# eth2rs485.net
KiCad netlist of a schematic drawn in EAGLE
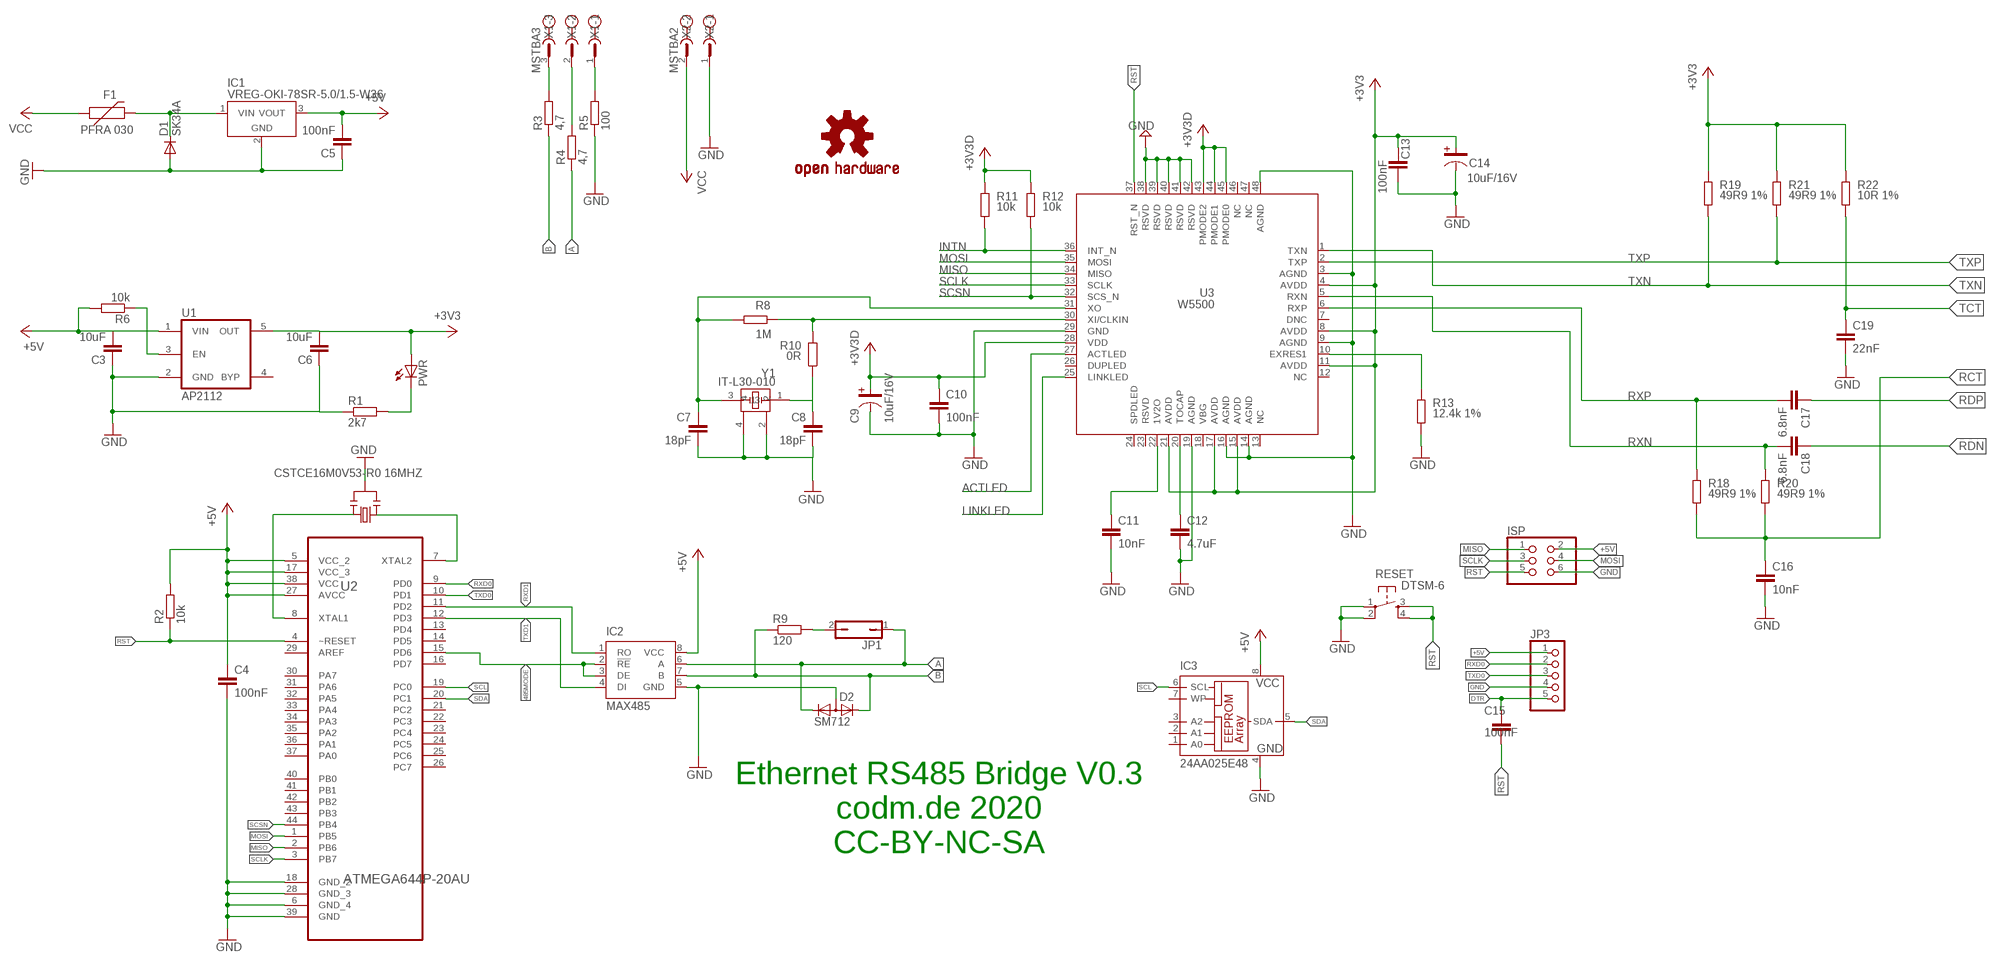
[diagram p0: schematic, sheet 1, part 1 of 2]
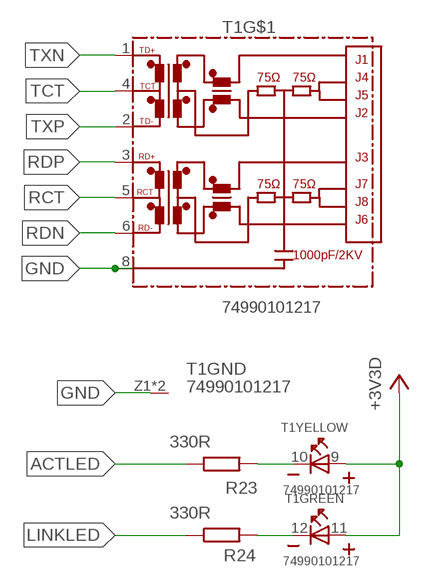
[diagram p1: schematic, sheet 1, part 2 of 2]

(export (version "E")
  (design (tool "Eeschema 10.0.6"))
  (components
    (comp (ref "C3")
      (value "10uF")
      (footprint "eagle-import:C0805")
      (libsource (lib "eagle-import") (part "C-EUC0805"))
    )
    (comp (ref "C4")
      (value "100nF")
      (footprint "eagle-import:C0805")
      (libsource (lib "eagle-import") (part "C-EUC0805"))
    )
    (comp (ref "C5")
      (value "100nF")
      (footprint "eagle-import:C0805")
      (libsource (lib "eagle-import") (part "C-EUC0805"))
    )
    (comp (ref "C6")
      (value "10uF")
      (footprint "eagle-import:C0805")
      (libsource (lib "eagle-import") (part "C-EUC0805"))
    )
    (comp (ref "C7")
      (value "18pF")
      (footprint "eagle-import:C0805")
      (libsource (lib "eagle-import") (part "C-EUC0805"))
    )
    (comp (ref "C8")
      (value "18pF")
      (footprint "eagle-import:C0805")
      (libsource (lib "eagle-import") (part "C-EUC0805"))
    )
    (comp (ref "C9")
      (value "10uF/16V")
      (footprint "eagle-import:C-3216(TANTAL)")
      (libsource (lib "eagle-import") (part "C-3216(TANTAL)"))
    )
    (comp (ref "C10")
      (value "100nF")
      (footprint "eagle-import:C0805")
      (libsource (lib "eagle-import") (part "C-EUC0805"))
    )
    (comp (ref "C11")
      (value "10nF")
      (footprint "eagle-import:C0805")
      (libsource (lib "eagle-import") (part "C-EUC0805"))
    )
    (comp (ref "C12")
      (value "4.7uF")
      (footprint "eagle-import:C0805")
      (libsource (lib "eagle-import") (part "C-EUC0805"))
    )
    (comp (ref "C13")
      (value "100nF")
      (footprint "eagle-import:C0805")
      (libsource (lib "eagle-import") (part "C-EUC0805"))
    )
    (comp (ref "C14")
      (value "10uF/16V")
      (footprint "eagle-import:C-3216(TANTAL)")
      (libsource (lib "eagle-import") (part "C-3216(TANTAL)"))
    )
    (comp (ref "C15")
      (value "100nF")
      (footprint "eagle-import:C0805")
      (libsource (lib "eagle-import") (part "C-EUC0805"))
    )
    (comp (ref "C16")
      (value "10nF")
      (footprint "eagle-import:C0805")
      (libsource (lib "eagle-import") (part "C-EUC0805"))
    )
    (comp (ref "C17")
      (value "6.8nF")
      (footprint "eagle-import:C0805")
      (libsource (lib "eagle-import") (part "C-EUC0805"))
    )
    (comp (ref "C18")
      (value "6.8nF")
      (footprint "eagle-import:C0805")
      (libsource (lib "eagle-import") (part "C-EUC0805"))
    )
    (comp (ref "C19")
      (value "22nF")
      (footprint "eagle-import:C0805")
      (libsource (lib "eagle-import") (part "C-EUC0805"))
    )
    (comp (ref "D1")
      (value "SK34A")
      (footprint "eagle-import:DO214AC")
      (libsource (lib "eagle-import") (part "DIODE-DO214AC"))
    )
    (comp (ref "D2")
      (value "SM712")
      (footprint "eagle-import:SOT23")
      (libsource (lib "eagle-import") (part "DIODE-2CA|ACSOT23"))
    )
    (comp (ref "F1")
      (value "PFRA 030")
      (footprint "eagle-import:PTH")
      (libsource (lib "eagle-import") (part "PPTC_PTH"))
    )
    (comp (ref "IC1")
      (value "VREG-OKI-78SR-5.0/1.5-W36")
      (footprint "eagle-import:OKI-78SR")
      (libsource (lib "eagle-import") (part "VREG-OKI-78SR-5.0/1.5-W36"))
    )
    (comp (ref "IC2")
      (value "MAX485")
      (footprint "eagle-import:SOIC8")
      (libsource (lib "eagle-import") (part "LTC485S"))
    )
    (comp (ref "IC3")
      (value "24AA025E48")
      (footprint "eagle-import:SO-08")
      (fields (field (name "MPN") "24AA02/SN"))
      (libsource (lib "eagle-import") (part "24SNAA02"))
    )
    (comp (ref "ISP")
      (value "PINHD-2X3")
      (footprint "eagle-import:2X03")
      (libsource (lib "eagle-import") (part "PINHD-2X3"))
    )
    (comp (ref "JP1")
      (value "JP1Q")
      (footprint "eagle-import:JP1")
      (libsource (lib "eagle-import") (part "JP1Q"))
    )
    (comp (ref "JP3")
      (value "PINHD-1X5")
      (footprint "eagle-import:1X05")
      (libsource (lib "eagle-import") (part "PINHD-1X5"))
    )
    (comp (ref "LOGO1")
      (value "OSHW-LOGOM")
      (footprint "eagle-import:OSHW-LOGO-M")
      (libsource (lib "eagle-import") (part "OSHW-LOGOM"))
    )
    (comp (ref "PWR")
      (value "LEDCHIP-LED0805")
      (footprint "eagle-import:CHIP-LED0805")
      (libsource (lib "eagle-import") (part "LEDCHIP-LED0805"))
    )
    (comp (ref "R1")
      (value "2k7")
      (footprint "eagle-import:R0805")
      (libsource (lib "eagle-import") (part "R-EU_R0805"))
    )
    (comp (ref "R2")
      (value "10k")
      (footprint "eagle-import:R0805")
      (libsource (lib "eagle-import") (part "R-EU_R0805"))
    )
    (comp (ref "R3")
      (value "4,7")
      (footprint "eagle-import:R0805")
      (libsource (lib "eagle-import") (part "R-EU_R0805"))
    )
    (comp (ref "R4")
      (value "4,7")
      (footprint "eagle-import:R0805")
      (libsource (lib "eagle-import") (part "R-EU_R0805"))
    )
    (comp (ref "R5")
      (value "100")
      (footprint "eagle-import:R0805")
      (libsource (lib "eagle-import") (part "R-EU_R0805"))
    )
    (comp (ref "R6")
      (value "10k")
      (footprint "eagle-import:R0805")
      (libsource (lib "eagle-import") (part "R-EU_R0805"))
    )
    (comp (ref "R8")
      (value "1M")
      (footprint "eagle-import:R0805")
      (libsource (lib "eagle-import") (part "R-EU_R0805"))
    )
    (comp (ref "R9")
      (value "120")
      (footprint "eagle-import:R0805")
      (libsource (lib "eagle-import") (part "R-EU_R0805"))
    )
    (comp (ref "R10")
      (value "0R")
      (footprint "eagle-import:R0805")
      (libsource (lib "eagle-import") (part "R-EU_R0805"))
    )
    (comp (ref "R11")
      (value "10k")
      (footprint "eagle-import:R0805")
      (libsource (lib "eagle-import") (part "R-EU_R0805"))
    )
    (comp (ref "R12")
      (value "10k")
      (footprint "eagle-import:R0805")
      (libsource (lib "eagle-import") (part "R-EU_R0805"))
    )
    (comp (ref "R13")
      (value "12.4k 1%")
      (footprint "eagle-import:R0805")
      (libsource (lib "eagle-import") (part "R-EU_R0805"))
    )
    (comp (ref "R18")
      (value "49R9 1%")
      (footprint "eagle-import:R0805")
      (libsource (lib "eagle-import") (part "R-EU_R0805"))
    )
    (comp (ref "R19")
      (value "49R9 1%")
      (footprint "eagle-import:R0805")
      (libsource (lib "eagle-import") (part "R-EU_R0805"))
    )
    (comp (ref "R20")
      (value "49R9 1%")
      (footprint "eagle-import:R0805")
      (libsource (lib "eagle-import") (part "R-EU_R0805"))
    )
    (comp (ref "R21")
      (value "49R9 1%")
      (footprint "eagle-import:R0805")
      (libsource (lib "eagle-import") (part "R-EU_R0805"))
    )
    (comp (ref "R22")
      (value "10R 1%")
      (footprint "eagle-import:R0805")
      (libsource (lib "eagle-import") (part "R-EU_R0805"))
    )
    (comp (ref "R23")
      (value "330R")
      (footprint "eagle-import:R0805")
      (libsource (lib "eagle-import") (part "R-EU_R0805"))
    )
    (comp (ref "R24")
      (value "330R")
      (footprint "eagle-import:R0805")
      (libsource (lib "eagle-import") (part "R-EU_R0805"))
    )
    (comp (ref "RESET")
      (value "DTSM-6")
      (footprint "eagle-import:DTSM-6")
      (libsource (lib "eagle-import") (part "DTSM-6"))
    )
    (comp (ref "T1")
      (value "74990101217")
      (footprint "eagle-import:74990111217")
      (libsource (lib "eagle-import") (part "WE-RJ45_74990111217"))
    )
    (comp (ref "U1")
      (value "AP2112")
      (footprint "eagle-import:SOT23-5")
      (libsource (lib "eagle-import") (part "AP2210K"))
    )
    (comp (ref "U2")
      (value "ATMEGA644P-20AU")
      (footprint "eagle-import:QFP80P1200X1200X120-44N")
      (libsource (lib "eagle-import") (part "ATMEGA644P-20AU"))
    )
    (comp (ref "U3")
      (value "W5500")
      (footprint "eagle-import:W5500")
      (libsource (lib "eagle-import") (part "W5500"))
    )
    (comp (ref "X1")
      (value "MSTBA3")
      (footprint "eagle-import:MSTBA3")
      (fields (field (name "MF") "FARNELL") (field (name "MPN") "1757255"))
      (libsource (lib "eagle-import") (part "MSTBA3"))
    )
    (comp (ref "X2")
      (value "MSTBA2")
      (footprint "eagle-import:MSTBA2")
      (fields (field (name "MF") "FARNELL") (field (name "MPN") "1757242"))
      (libsource (lib "eagle-import") (part "MSTBA2"))
    )
    (comp (ref "Y1")
      (value "IT-L30-010")
      (footprint "eagle-import:IT-L30-010")
      (libsource (lib "eagle-import") (part "IT-L30-010"))
    )
    (comp (ref "Y2")
      (value "CSTCE16M0V53-R0 16MHZ")
      (footprint "eagle-import:RESONATOR")
      (libsource (lib "eagle-import") (part "RESONATORMU"))
    )
  )
  (nets
    (net (code "1") (name "+3V3") (class "Default")
      (node (ref "C10") (pin "1") (pinfunction "1_1") (pintype "passive"))
      (node (ref "C13") (pin "1") (pinfunction "1_1") (pintype "passive"))
      (node (ref "C14") (pin "1") (pinfunction "1_1") (pintype "passive"))
      (node (ref "C6") (pin "2") (pinfunction "2_2") (pintype "passive"))
      (node (ref "C9") (pin "1") (pinfunction "1_1") (pintype "passive"))
      (node (ref "PWR") (pin "A") (pinfunction "A_A") (pintype "passive"))
      (node (ref "R11") (pin "2") (pinfunction "2_2") (pintype "passive"))
      (node (ref "R12") (pin "2") (pinfunction "2_2") (pintype "passive"))
      (node (ref "R19") (pin "2") (pinfunction "2_2") (pintype "passive"))
      (node (ref "R21") (pin "2") (pinfunction "2_2") (pintype "passive"))
      (node (ref "R22") (pin "2") (pinfunction "2_2") (pintype "passive"))
      (node (ref "T1") (pin "11") (pinfunction "A_11") (pintype "passive"))
      (node (ref "T1") (pin "9") (pinfunction "A_9") (pintype "passive"))
      (node (ref "U1") (pin "5") (pinfunction "OUT_5") (pintype "power_in"))
      (node (ref "U3") (pin "11") (pinfunction "AVDD_11") (pintype "passive"))
      (node (ref "U3") (pin "15") (pinfunction "AVDD_15") (pintype "passive"))
      (node (ref "U3") (pin "17") (pinfunction "AVDD_17") (pintype "passive"))
      (node (ref "U3") (pin "21") (pinfunction "AVDD_21") (pintype "passive"))
      (node (ref "U3") (pin "28") (pinfunction "VDD_28") (pintype "passive"))
      (node (ref "U3") (pin "4") (pinfunction "AVDD_4") (pintype "passive"))
      (node (ref "U3") (pin "43") (pinfunction "PMODE2_43") (pintype "passive"))
      (node (ref "U3") (pin "44") (pinfunction "PMODE1_44") (pintype "passive"))
      (node (ref "U3") (pin "45") (pinfunction "PMODE0_45") (pintype "passive"))
      (node (ref "U3") (pin "8") (pinfunction "AVDD_8") (pintype "passive"))
    )
    (net (code "2") (name "+5V") (class "Default")
      (node (ref "C3") (pin "2") (pinfunction "2_2") (pintype "passive"))
      (node (ref "C4") (pin "1") (pinfunction "1_1") (pintype "passive"))
      (node (ref "C5") (pin "2") (pinfunction "2_2") (pintype "passive"))
      (node (ref "IC1") (pin "3") (pinfunction "VOUT_3") (pintype "power_in"))
      (node (ref "IC2") (pin "8") (pinfunction "VCC_8") (pintype "input"))
      (node (ref "IC3") (pin "8") (pinfunction "VCC_8") (pintype "power_in"))
      (node (ref "ISP") (pin "2") (pinfunction "2_2") (pintype "passive"))
      (node (ref "JP3") (pin "1") (pinfunction "1_1") (pintype "passive"))
      (node (ref "R2") (pin "2") (pinfunction "2_2") (pintype "passive"))
      (node (ref "R6") (pin "2") (pinfunction "2_2") (pintype "passive"))
      (node (ref "U1") (pin "1") (pinfunction "VIN_1") (pintype "input"))
      (node (ref "U2") (pin "17") (pinfunction "VCC_3_17") (pintype "power_in"))
      (node (ref "U2") (pin "27") (pinfunction "AVCC_27") (pintype "power_in"))
      (node (ref "U2") (pin "38") (pinfunction "VCC_38") (pintype "power_in"))
      (node (ref "U2") (pin "5") (pinfunction "VCC_2_5") (pintype "power_in"))
    )
    (net (code "3") (name "/INTN") (class "Default")
      (node (ref "R11") (pin "1") (pinfunction "1_1") (pintype "passive"))
      (node (ref "U3") (pin "36") (pinfunction "INT_N_36") (pintype "passive"))
    )
    (net (code "4") (name "/RXN") (class "Default")
      (node (ref "C18") (pin "2") (pinfunction "2_2") (pintype "passive"))
      (node (ref "R20") (pin "2") (pinfunction "2_2") (pintype "passive"))
      (node (ref "U3") (pin "5") (pinfunction "RXN_5") (pintype "passive"))
    )
    (net (code "5") (name "/RXP") (class "Default")
      (node (ref "C17") (pin "2") (pinfunction "2_2") (pintype "passive"))
      (node (ref "R18") (pin "2") (pinfunction "2_2") (pintype "passive"))
      (node (ref "U3") (pin "6") (pinfunction "RXP_6") (pintype "passive"))
    )
    (net (code "6") (name "485MODE") (class "Default")
      (node (ref "IC2") (pin "2") (pinfunction "~{RE}_2") (pintype "input"))
      (node (ref "IC2") (pin "3") (pinfunction "DE_3") (pintype "input"))
      (node (ref "U2") (pin "15") (pinfunction "PD6_15") (pintype "bidirectional"))
    )
    (net (code "7") (name "A") (class "Default")
      (node (ref "D2") (pin "1") (pinfunction "K1_1") (pintype "passive"))
      (node (ref "IC2") (pin "6") (pinfunction "A_6") (pintype "bidirectional"))
      (node (ref "JP1") (pin "1") (pinfunction "1_1") (pintype "passive"))
      (node (ref "R4") (pin "1") (pinfunction "1_1") (pintype "passive"))
    )
    (net (code "8") (name "ACTLED") (class "Default")
      (node (ref "R23") (pin "1") (pinfunction "1_1") (pintype "passive"))
      (node (ref "U3") (pin "27") (pinfunction "ACTLED_27") (pintype "passive"))
    )
    (net (code "9") (name "B") (class "Default")
      (node (ref "D2") (pin "2") (pinfunction "K2_2") (pintype "passive"))
      (node (ref "IC2") (pin "7") (pinfunction "B_7") (pintype "bidirectional"))
      (node (ref "R3") (pin "1") (pinfunction "1_1") (pintype "passive"))
      (node (ref "R9") (pin "1") (pinfunction "1_1") (pintype "passive"))
    )
    (net (code "10") (name "DTR") (class "Default")
      (node (ref "C15") (pin "1") (pinfunction "1_1") (pintype "passive"))
      (node (ref "JP3") (pin "5") (pinfunction "5_5") (pintype "passive"))
    )
    (net (code "11") (name "GND") (class "Default")
      (node (ref "C10") (pin "2") (pinfunction "2_2") (pintype "passive"))
      (node (ref "C11") (pin "2") (pinfunction "2_2") (pintype "passive"))
      (node (ref "C12") (pin "2") (pinfunction "2_2") (pintype "passive"))
      (node (ref "C13") (pin "2") (pinfunction "2_2") (pintype "passive"))
      (node (ref "C14") (pin "2") (pinfunction "2_2") (pintype "passive"))
      (node (ref "C16") (pin "2") (pinfunction "2_2") (pintype "passive"))
      (node (ref "C19") (pin "2") (pinfunction "2_2") (pintype "passive"))
      (node (ref "C3") (pin "1") (pinfunction "1_1") (pintype "passive"))
      (node (ref "C4") (pin "2") (pinfunction "2_2") (pintype "passive"))
      (node (ref "C5") (pin "1") (pinfunction "1_1") (pintype "passive"))
      (node (ref "C6") (pin "1") (pinfunction "1_1") (pintype "passive"))
      (node (ref "C7") (pin "2") (pinfunction "2_2") (pintype "passive"))
      (node (ref "C8") (pin "2") (pinfunction "2_2") (pintype "passive"))
      (node (ref "C9") (pin "2") (pinfunction "2_2") (pintype "passive"))
      (node (ref "D1") (pin "A") (pinfunction "A_A") (pintype "passive"))
      (node (ref "D2") (pin "3") (pinfunction "A_3") (pintype "passive"))
      (node (ref "IC1") (pin "2") (pinfunction "GND_2") (pintype "power_in"))
      (node (ref "IC2") (pin "5") (pinfunction "GND_5") (pintype "input"))
      (node (ref "IC3") (pin "4") (pinfunction "GND_4") (pintype "power_in"))
      (node (ref "ISP") (pin "6") (pinfunction "6_6") (pintype "passive"))
      (node (ref "JP3") (pin "4") (pinfunction "4_4") (pintype "passive"))
      (node (ref "R1") (pin "1") (pinfunction "1_1") (pintype "passive"))
      (node (ref "R13") (pin "1") (pinfunction "1_1") (pintype "passive"))
      (node (ref "R5") (pin "1") (pinfunction "1_1") (pintype "passive"))
      (node (ref "RESET") (pin "1") (pinfunction "1_1") (pintype "passive"))
      (node (ref "RESET") (pin "2") (pinfunction "2_2") (pintype "passive"))
      (node (ref "T1") (pin "8") (pinfunction "8_8") (pintype "bidirectional"))
      (node (ref "T1") (pin "Z1") (pinfunction "GND_Z1") (pintype "power_in"))
      (node (ref "T1") (pin "Z2") (pinfunction "GND_Z2") (pintype "power_in"))
      (node (ref "U1") (pin "2") (pinfunction "GND_2") (pintype "power_in"))
      (node (ref "U2") (pin "18") (pinfunction "GND_2_18") (pintype "passive"))
      (node (ref "U2") (pin "28") (pinfunction "GND_3_28") (pintype "passive"))
      (node (ref "U2") (pin "39") (pinfunction "GND_39") (pintype "passive"))
      (node (ref "U2") (pin "6") (pinfunction "GND_4_6") (pintype "passive"))
      (node (ref "U3") (pin "14") (pinfunction "AGND_14") (pintype "passive"))
      (node (ref "U3") (pin "16") (pinfunction "AGND_16") (pintype "passive"))
      (node (ref "U3") (pin "19") (pinfunction "AGND_19") (pintype "passive"))
      (node (ref "U3") (pin "29") (pinfunction "GND_29") (pintype "passive"))
      (node (ref "U3") (pin "3") (pinfunction "AGND_3") (pintype "passive"))
      (node (ref "U3") (pin "38") (pinfunction "RSVD_38") (pintype "passive"))
      (node (ref "U3") (pin "39") (pinfunction "RSVD_39") (pintype "passive"))
      (node (ref "U3") (pin "40") (pinfunction "RSVD_40") (pintype "passive"))
      (node (ref "U3") (pin "41") (pinfunction "RSVD_41") (pintype "passive"))
      (node (ref "U3") (pin "42") (pinfunction "RSVD_42") (pintype "passive"))
      (node (ref "U3") (pin "48") (pinfunction "AGND_48") (pintype "passive"))
      (node (ref "U3") (pin "9") (pinfunction "AGND_9") (pintype "passive"))
      (node (ref "X2") (pin "1") (pinfunction "1_1") (pintype "passive"))
      (node (ref "Y1") (pin "2") (pinfunction "2_2") (pintype "passive"))
      (node (ref "Y1") (pin "4") (pinfunction "4_4") (pintype "passive"))
      (node (ref "Y2") (pin "2") (pinfunction "2_2") (pintype "passive"))
    )
    (net (code "12") (name "LINKLED") (class "Default")
      (node (ref "R24") (pin "1") (pinfunction "1_1") (pintype "passive"))
      (node (ref "U3") (pin "25") (pinfunction "LINKLED_25") (pintype "passive"))
    )
    (net (code "13") (name "MISO") (class "Default")
      (node (ref "ISP") (pin "1") (pinfunction "1_1") (pintype "passive"))
      (node (ref "U2") (pin "2") (pinfunction "PB6_2") (pintype "bidirectional"))
      (node (ref "U3") (pin "34") (pinfunction "MISO_34") (pintype "passive"))
    )
    (net (code "14") (name "MOSI") (class "Default")
      (node (ref "ISP") (pin "4") (pinfunction "4_4") (pintype "passive"))
      (node (ref "U2") (pin "1") (pinfunction "PB5_1") (pintype "bidirectional"))
      (node (ref "U3") (pin "35") (pinfunction "MOSI_35") (pintype "passive"))
    )
    (net (code "15") (name "Net-(C8-Pad1)") (class "Default")
      (node (ref "C8") (pin "1") (pinfunction "1_1") (pintype "passive"))
      (node (ref "R10") (pin "1") (pinfunction "1_1") (pintype "passive"))
      (node (ref "Y1") (pin "1") (pinfunction "1_1") (pintype "passive"))
    )
    (net (code "16") (name "Net-(F1-2)") (class "Default")
      (node (ref "D1") (pin "C") (pinfunction "C_C") (pintype "passive"))
      (node (ref "F1") (pin "P$2") (pinfunction "2_P$2") (pintype "bidirectional"))
      (node (ref "IC1") (pin "1") (pinfunction "VIN_1") (pintype "power_in"))
    )
    (net (code "17") (name "Net-(JP1-Pad2)") (class "Default")
      (node (ref "JP1") (pin "2") (pinfunction "2_2") (pintype "passive"))
      (node (ref "R9") (pin "2") (pinfunction "2_2") (pintype "passive"))
    )
    (net (code "18") (name "Net-(PWR-PadC)") (class "Default")
      (node (ref "PWR") (pin "C") (pinfunction "C_C") (pintype "passive"))
      (node (ref "R1") (pin "2") (pinfunction "2_2") (pintype "passive"))
    )
    (net (code "19") (name "Net-(R5-Pad2)") (class "Default")
      (node (ref "R5") (pin "2") (pinfunction "2_2") (pintype "passive"))
      (node (ref "X1") (pin "1") (pinfunction "1_1") (pintype "passive"))
    )
    (net (code "20") (name "Net-(T1C-K)") (class "Default")
      (node (ref "R24") (pin "2") (pinfunction "2_2") (pintype "passive"))
      (node (ref "T1") (pin "12") (pinfunction "K_12") (pintype "passive"))
    )
    (net (code "21") (name "Net-(T1D-K)") (class "Default")
      (node (ref "R23") (pin "2") (pinfunction "2_2") (pintype "passive"))
      (node (ref "T1") (pin "10") (pinfunction "K_10") (pintype "passive"))
    )
    (net (code "22") (name "Net-(U1-EN)") (class "Default")
      (node (ref "R6") (pin "1") (pinfunction "1_1") (pintype "passive"))
      (node (ref "U1") (pin "3") (pinfunction "EN_3") (pintype "input"))
    )
    (net (code "23") (name "Net-(U2-XTAL1)") (class "Default")
      (node (ref "U2") (pin "8") (pinfunction "XTAL1_8") (pintype "input"))
      (node (ref "Y2") (pin "3") (pinfunction "3_3") (pintype "passive"))
    )
    (net (code "24") (name "Net-(U2-XTAL2)") (class "Default")
      (node (ref "U2") (pin "7") (pinfunction "XTAL2_7") (pintype "output"))
      (node (ref "Y2") (pin "1") (pinfunction "1_1") (pintype "passive"))
    )
    (net (code "25") (name "Net-(U3-1V2O)") (class "Default")
      (node (ref "C11") (pin "1") (pinfunction "1_1") (pintype "passive"))
      (node (ref "U3") (pin "22") (pinfunction "1V2O_22") (pintype "passive"))
    )
    (net (code "26") (name "Net-(U3-EXRES1)") (class "Default")
      (node (ref "R13") (pin "2") (pinfunction "2_2") (pintype "passive"))
      (node (ref "U3") (pin "10") (pinfunction "EXRES1_10") (pintype "passive"))
    )
    (net (code "27") (name "Net-(U3-TOCAP)") (class "Default")
      (node (ref "C12") (pin "1") (pinfunction "1_1") (pintype "passive"))
      (node (ref "U3") (pin "20") (pinfunction "TOCAP_20") (pintype "passive"))
    )
    (net (code "28") (name "Net-(U3-XI{slash}CLKIN)") (class "Default")
      (node (ref "R10") (pin "2") (pinfunction "2_2") (pintype "passive"))
      (node (ref "R8") (pin "2") (pinfunction "2_2") (pintype "passive"))
      (node (ref "U3") (pin "30") (pinfunction "XI/CLKIN_30") (pintype "passive"))
    )
    (net (code "29") (name "Net-(U3-XO)") (class "Default")
      (node (ref "C7") (pin "1") (pinfunction "1_1") (pintype "passive"))
      (node (ref "R8") (pin "1") (pinfunction "1_1") (pintype "passive"))
      (node (ref "U3") (pin "31") (pinfunction "XO_31") (pintype "passive"))
      (node (ref "Y1") (pin "3") (pinfunction "3_3") (pintype "passive"))
    )
    (net (code "30") (name "Net-(X1B-1)") (class "Default")
      (node (ref "R4") (pin "2") (pinfunction "2_2") (pintype "passive"))
      (node (ref "X1") (pin "2") (pinfunction "1_2") (pintype "passive"))
    )
    (net (code "31") (name "Net-(X1C-1)") (class "Default")
      (node (ref "R3") (pin "2") (pinfunction "2_2") (pintype "passive"))
      (node (ref "X1") (pin "3") (pinfunction "1_3") (pintype "passive"))
    )
    (net (code "32") (name "RCT") (class "Default")
      (node (ref "C16") (pin "1") (pinfunction "1_1") (pintype "passive"))
      (node (ref "R18") (pin "1") (pinfunction "1_1") (pintype "passive"))
      (node (ref "R20") (pin "1") (pinfunction "1_1") (pintype "passive"))
      (node (ref "T1") (pin "5") (pinfunction "RCT_5") (pintype "bidirectional"))
    )
    (net (code "33") (name "RDN") (class "Default")
      (node (ref "C18") (pin "1") (pinfunction "1_1") (pintype "passive"))
      (node (ref "T1") (pin "6") (pinfunction "RD-_6") (pintype "bidirectional"))
    )
    (net (code "34") (name "RDP") (class "Default")
      (node (ref "C17") (pin "1") (pinfunction "1_1") (pintype "passive"))
      (node (ref "T1") (pin "3") (pinfunction "RD+_3") (pintype "bidirectional"))
    )
    (net (code "35") (name "RST") (class "Default")
      (node (ref "C15") (pin "2") (pinfunction "2_2") (pintype "passive"))
      (node (ref "ISP") (pin "5") (pinfunction "5_5") (pintype "passive"))
      (node (ref "R2") (pin "1") (pinfunction "1_1") (pintype "passive"))
      (node (ref "RESET") (pin "3") (pinfunction "3_3") (pintype "passive"))
      (node (ref "RESET") (pin "4") (pinfunction "4_4") (pintype "passive"))
      (node (ref "U2") (pin "4") (pinfunction "~{RESET}_4") (pintype "input"))
      (node (ref "U3") (pin "37") (pinfunction "RST_N_37") (pintype "passive"))
    )
    (net (code "36") (name "RXD0") (class "Default")
      (node (ref "JP3") (pin "2") (pinfunction "2_2") (pintype "passive"))
      (node (ref "U2") (pin "9") (pinfunction "PD0_9") (pintype "bidirectional"))
    )
    (net (code "37") (name "RXD1") (class "Default")
      (node (ref "IC2") (pin "1") (pinfunction "RO_1") (pintype "output"))
      (node (ref "U2") (pin "11") (pinfunction "PD2_11") (pintype "bidirectional"))
    )
    (net (code "38") (name "SCL") (class "Default")
      (node (ref "IC3") (pin "6") (pinfunction "SCL_6") (pintype "input"))
      (node (ref "U2") (pin "19") (pinfunction "PC0_19") (pintype "bidirectional"))
    )
    (net (code "39") (name "SCLK") (class "Default")
      (node (ref "ISP") (pin "3") (pinfunction "3_3") (pintype "passive"))
      (node (ref "U2") (pin "3") (pinfunction "PB7_3") (pintype "bidirectional"))
      (node (ref "U3") (pin "33") (pinfunction "SCLK_33") (pintype "passive"))
    )
    (net (code "40") (name "SCSN") (class "Default")
      (node (ref "R12") (pin "1") (pinfunction "1_1") (pintype "passive"))
      (node (ref "U2") (pin "44") (pinfunction "PB4_44") (pintype "bidirectional"))
      (node (ref "U3") (pin "32") (pinfunction "SCS_N_32") (pintype "passive"))
    )
    (net (code "41") (name "SDA") (class "Default")
      (node (ref "IC3") (pin "5") (pinfunction "SDA_5") (pintype "bidirectional"))
      (node (ref "U2") (pin "20") (pinfunction "PC1_20") (pintype "bidirectional"))
    )
    (net (code "42") (name "TCT") (class "Default")
      (node (ref "C19") (pin "1") (pinfunction "1_1") (pintype "passive"))
      (node (ref "R22") (pin "1") (pinfunction "1_1") (pintype "passive"))
      (node (ref "T1") (pin "4") (pinfunction "TCT_4") (pintype "bidirectional"))
    )
    (net (code "43") (name "TXD0") (class "Default")
      (node (ref "JP3") (pin "3") (pinfunction "3_3") (pintype "passive"))
      (node (ref "U2") (pin "10") (pinfunction "PD1_10") (pintype "bidirectional"))
    )
    (net (code "44") (name "TXD1") (class "Default")
      (node (ref "IC2") (pin "4") (pinfunction "DI_4") (pintype "input"))
      (node (ref "U2") (pin "12") (pinfunction "PD3_12") (pintype "bidirectional"))
    )
    (net (code "45") (name "TXN") (class "Default")
      (node (ref "R19") (pin "1") (pinfunction "1_1") (pintype "passive"))
      (node (ref "T1") (pin "1") (pinfunction "TD+_1") (pintype "bidirectional"))
      (node (ref "U3") (pin "1") (pinfunction "TXN_1") (pintype "passive"))
    )
    (net (code "46") (name "TXP") (class "Default")
      (node (ref "R21") (pin "1") (pinfunction "1_1") (pintype "passive"))
      (node (ref "T1") (pin "2") (pinfunction "TD-_2") (pintype "bidirectional"))
      (node (ref "U3") (pin "2") (pinfunction "TXP_2") (pintype "passive"))
    )
    (net (code "47") (name "VCC") (class "Default")
      (node (ref "F1") (pin "P$1") (pinfunction "1_P$1") (pintype "bidirectional"))
      (node (ref "X2") (pin "2") (pinfunction "1_2") (pintype "passive"))
    )
    (net (code "48") (name "unconnected-(IC3-A0-Pad1)") (class "Default")
      (node (ref "IC3") (pin "1") (pinfunction "A0_1") (pintype "input"))
    )
    (net (code "49") (name "unconnected-(IC3-A1-Pad2)") (class "Default")
      (node (ref "IC3") (pin "2") (pinfunction "A1_2") (pintype "input"))
    )
    (net (code "50") (name "unconnected-(IC3-A2-Pad3)") (class "Default")
      (node (ref "IC3") (pin "3") (pinfunction "A2_3") (pintype "input"))
    )
    (net (code "51") (name "unconnected-(IC3-WP-Pad7)") (class "Default")
      (node (ref "IC3") (pin "7") (pinfunction "WP_7") (pintype "input"))
    )
    (net (code "52") (name "unconnected-(U1-BYP-Pad4)") (class "Default")
      (node (ref "U1") (pin "4") (pinfunction "BYP_4") (pintype "output"))
    )
    (net (code "53") (name "unconnected-(U2-AREF-Pad29)") (class "Default")
      (node (ref "U2") (pin "29") (pinfunction "AREF_29") (pintype "input"))
    )
    (net (code "54") (name "unconnected-(U2-PA0-Pad37)") (class "Default")
      (node (ref "U2") (pin "37") (pinfunction "PA0_37") (pintype "bidirectional"))
    )
    (net (code "55") (name "unconnected-(U2-PA1-Pad36)") (class "Default")
      (node (ref "U2") (pin "36") (pinfunction "PA1_36") (pintype "bidirectional"))
    )
    (net (code "56") (name "unconnected-(U2-PA2-Pad35)") (class "Default")
      (node (ref "U2") (pin "35") (pinfunction "PA2_35") (pintype "bidirectional"))
    )
    (net (code "57") (name "unconnected-(U2-PA3-Pad34)") (class "Default")
      (node (ref "U2") (pin "34") (pinfunction "PA3_34") (pintype "bidirectional"))
    )
    (net (code "58") (name "unconnected-(U2-PA4-Pad33)") (class "Default")
      (node (ref "U2") (pin "33") (pinfunction "PA4_33") (pintype "bidirectional"))
    )
    (net (code "59") (name "unconnected-(U2-PA5-Pad32)") (class "Default")
      (node (ref "U2") (pin "32") (pinfunction "PA5_32") (pintype "bidirectional"))
    )
    (net (code "60") (name "unconnected-(U2-PA6-Pad31)") (class "Default")
      (node (ref "U2") (pin "31") (pinfunction "PA6_31") (pintype "bidirectional"))
    )
    (net (code "61") (name "unconnected-(U2-PA7-Pad30)") (class "Default")
      (node (ref "U2") (pin "30") (pinfunction "PA7_30") (pintype "bidirectional"))
    )
    (net (code "62") (name "unconnected-(U2-PB0-Pad40)") (class "Default")
      (node (ref "U2") (pin "40") (pinfunction "PB0_40") (pintype "bidirectional"))
    )
    (net (code "63") (name "unconnected-(U2-PB1-Pad41)") (class "Default")
      (node (ref "U2") (pin "41") (pinfunction "PB1_41") (pintype "bidirectional"))
    )
    (net (code "64") (name "unconnected-(U2-PB2-Pad42)") (class "Default")
      (node (ref "U2") (pin "42") (pinfunction "PB2_42") (pintype "bidirectional"))
    )
    (net (code "65") (name "unconnected-(U2-PB3-Pad43)") (class "Default")
      (node (ref "U2") (pin "43") (pinfunction "PB3_43") (pintype "bidirectional"))
    )
    (net (code "66") (name "unconnected-(U2-PC2-Pad21)") (class "Default")
      (node (ref "U2") (pin "21") (pinfunction "PC2_21") (pintype "bidirectional"))
    )
    (net (code "67") (name "unconnected-(U2-PC3-Pad22)") (class "Default")
      (node (ref "U2") (pin "22") (pinfunction "PC3_22") (pintype "bidirectional"))
    )
    (net (code "68") (name "unconnected-(U2-PC4-Pad23)") (class "Default")
      (node (ref "U2") (pin "23") (pinfunction "PC4_23") (pintype "bidirectional"))
    )
    (net (code "69") (name "unconnected-(U2-PC5-Pad24)") (class "Default")
      (node (ref "U2") (pin "24") (pinfunction "PC5_24") (pintype "bidirectional"))
    )
    (net (code "70") (name "unconnected-(U2-PC6-Pad25)") (class "Default")
      (node (ref "U2") (pin "25") (pinfunction "PC6_25") (pintype "bidirectional"))
    )
    (net (code "71") (name "unconnected-(U2-PC7-Pad26)") (class "Default")
      (node (ref "U2") (pin "26") (pinfunction "PC7_26") (pintype "bidirectional"))
    )
    (net (code "72") (name "unconnected-(U2-PD4-Pad13)") (class "Default")
      (node (ref "U2") (pin "13") (pinfunction "PD4_13") (pintype "bidirectional"))
    )
    (net (code "73") (name "unconnected-(U2-PD5-Pad14)") (class "Default")
      (node (ref "U2") (pin "14") (pinfunction "PD5_14") (pintype "bidirectional"))
    )
    (net (code "74") (name "unconnected-(U2-PD7-Pad16)") (class "Default")
      (node (ref "U2") (pin "16") (pinfunction "PD7_16") (pintype "bidirectional"))
    )
    (net (code "75") (name "unconnected-(U3-DNC-Pad7)") (class "Default")
      (node (ref "U3") (pin "7") (pinfunction "DNC_7") (pintype "passive"))
    )
    (net (code "76") (name "unconnected-(U3-DUPLED-Pad26)") (class "Default")
      (node (ref "U3") (pin "26") (pinfunction "DUPLED_26") (pintype "passive"))
    )
    (net (code "77") (name "unconnected-(U3-NC-Pad12)") (class "Default")
      (node (ref "U3") (pin "12") (pinfunction "NC_12") (pintype "passive"))
    )
    (net (code "78") (name "unconnected-(U3-NC-Pad13)") (class "Default")
      (node (ref "U3") (pin "13") (pinfunction "NC_13") (pintype "passive"))
    )
    (net (code "79") (name "unconnected-(U3-NC-Pad46)") (class "Default")
      (node (ref "U3") (pin "46") (pinfunction "NC_46") (pintype "passive"))
    )
    (net (code "80") (name "unconnected-(U3-NC-Pad47)") (class "Default")
      (node (ref "U3") (pin "47") (pinfunction "NC_47") (pintype "passive"))
    )
    (net (code "81") (name "unconnected-(U3-RSVD-Pad23)") (class "Default")
      (node (ref "U3") (pin "23") (pinfunction "RSVD_23") (pintype "passive"))
    )
    (net (code "82") (name "unconnected-(U3-SPDLED-Pad24)") (class "Default")
      (node (ref "U3") (pin "24") (pinfunction "SPDLED_24") (pintype "passive"))
    )
    (net (code "83") (name "unconnected-(U3-VBG-Pad18)") (class "Default")
      (node (ref "U3") (pin "18") (pinfunction "VBG_18") (pintype "passive"))
    )
  )
)
